# OpenMPPT2-DEBUG.net
KiCad netlist of a schematic drawn in Altium Designer
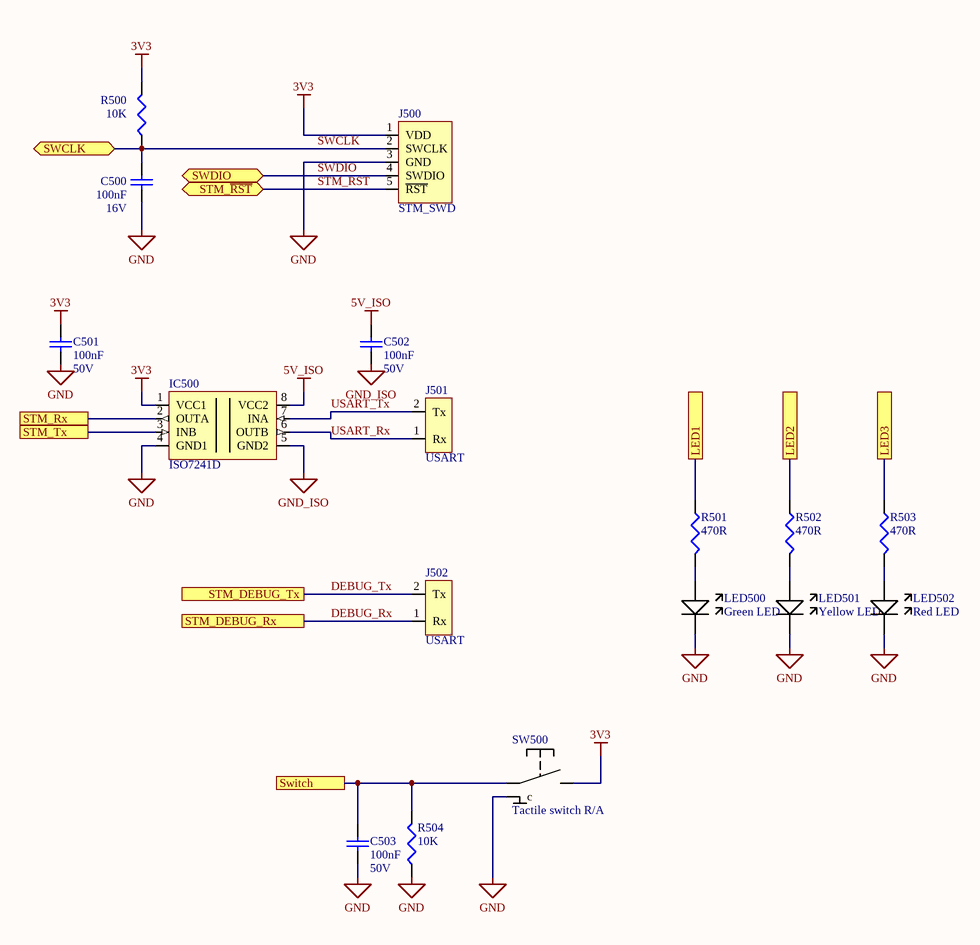
[diagram p0: OpenMPPT2-DEBUG.SchDoc]

(export (version "E")
  (design (tool "Eeschema 10.0.6"))
  (components
    (comp (ref "C500")
      (value "100nF")
      (footprint "C0603")
      (description "Capacitor, 100nF, 16V, X7R")
      (fields (field (name "VOLTAGE RATING") "16V"))
      (libsource (lib "SBT_Capacitors_Ceramic") (part "100nF/0603/CER/16V"))
    )
    (comp (ref "C501")
      (value "100nF")
      (footprint "C0603")
      (description "Capacitor, 100nF, 50V, X7R")
      (fields (field (name "VOLTAGE RATING") "50V"))
      (libsource (lib "SBT_Capacitors_Ceramic") (part "100nF/0603/CER/50V"))
    )
    (comp (ref "C502")
      (value "100nF")
      (footprint "C0603")
      (description "Capacitor, 100nF, 50V, X7R")
      (fields (field (name "VOLTAGE RATING") "50V"))
      (libsource (lib "SBT_Capacitors_Ceramic") (part "100nF/0603/CER/50V"))
    )
    (comp (ref "C503")
      (value "100nF")
      (footprint "C0603")
      (description "Capacitor, 100nF, 50V, X7R")
      (fields (field (name "VOLTAGE RATING") "50V"))
      (libsource (lib "SBT_Capacitors_Ceramic") (part "100nF/0603/CER/50V"))
    )
    (comp (ref "IC500")
      (value "ISO7241D")
      (footprint "SO-8")
      (description "1/1, 1Mbps Digital Isolator")
      (libsource (lib "SBT_ICs") (part "ISO7241D"))
    )
    (comp (ref "J500")
      (value "STM_SWD")
      (footprint "Header 2.54 5p")
      (description "SWD connector compliant with STM32 Nucleo boards")
      (libsource (lib "SBT_Connectors") (part "STM_SWD"))
    )
    (comp (ref "J501")
      (value "USART")
      (footprint "HEADER 2.54mm 2pin")
      (libsource (lib "SBT_Connectors") (part "USART"))
    )
    (comp (ref "J502")
      (value "USART")
      (footprint "HEADER 2.54mm 2pin")
      (libsource (lib "SBT_Connectors") (part "USART"))
    )
    (comp (ref "LED500")
      (value "Green LED")
      (footprint "0603")
      (description "LED, Green, 0603")
      (libsource (lib "SBT_LEDs") (part "KPT-1608SGC"))
    )
    (comp (ref "LED501")
      (value "Yellow LED")
      (footprint "0603")
      (description "LED, Yellow, 0603")
      (libsource (lib "SBT_LEDs") (part "KPT-2012YC"))
    )
    (comp (ref "LED502")
      (value "Red LED")
      (footprint "0603")
      (description "LED, Red, 0603")
      (libsource (lib "SBT_LEDs") (part "KPT-2012EC"))
    )
    (comp (ref "R500")
      (value "10K")
      (footprint "0603")
      (description "Resistor, 10K, 1%, 0.063W, 50V, 100PPM, 0603")
      (libsource (lib "SBT_Resistors_SMD") (part "10K/0603/0063W/50V"))
    )
    (comp (ref "R501")
      (value "470R")
      (footprint "0603")
      (description "Resistor, 470R, 1%, 0.125W, 50V, 100PPM, 0603")
      (libsource (lib "SBT_Resistors_SMD") (part "470/0603/0125W/50V"))
    )
    (comp (ref "R502")
      (value "470R")
      (footprint "0603")
      (description "Resistor, 470R, 1%, 0.125W, 50V, 100PPM, 0603")
      (libsource (lib "SBT_Resistors_SMD") (part "470/0603/0125W/50V"))
    )
    (comp (ref "R503")
      (value "470R")
      (footprint "0603")
      (description "Resistor, 470R, 1%, 0.125W, 50V, 100PPM, 0603")
      (libsource (lib "SBT_Resistors_SMD") (part "470/0603/0125W/50V"))
    )
    (comp (ref "R504")
      (value "10K")
      (footprint "0603")
      (description "Resistor, 10K, 1%, 0.063W, 50V, 100PPM, 0603")
      (libsource (lib "SBT_Resistors_SMD") (part "10K/0603/0063W/50V"))
    )
    (comp (ref "SW500")
      (value "Tactile switch R/A")
      (footprint "TactSW RA")
      (description "Tactile switch angled")
      (libsource (lib "SBT_DannyLib") (part "TactSwitch"))
    )
  )
  (nets
    (net (code "1") (name "/DEBUG_Rx") (class "Default")
      (node (ref "J502") (pin "1") (pinfunction "Rx_1") (pintype "passive"))
    )
    (net (code "2") (name "/DEBUG_Tx") (class "Default")
      (node (ref "J502") (pin "2") (pinfunction "Tx_2") (pintype "passive"))
    )
    (net (code "3") (name "/LED1") (class "Default")
      (node (ref "R501") (pin "1") (pinfunction "1_1") (pintype "passive"))
    )
    (net (code "4") (name "/LED2") (class "Default")
      (node (ref "R502") (pin "1") (pinfunction "1_1") (pintype "passive"))
    )
    (net (code "5") (name "/LED3") (class "Default")
      (node (ref "R503") (pin "1") (pinfunction "1_1") (pintype "passive"))
    )
    (net (code "6") (name "/STM_Rx") (class "Default")
      (node (ref "IC500") (pin "2") (pinfunction "OUTA_2") (pintype "output"))
    )
    (net (code "7") (name "/STM_Tx") (class "Default")
      (node (ref "IC500") (pin "3") (pinfunction "INB_3") (pintype "input"))
    )
    (net (code "8") (name "/STM_~{RST}") (class "Default")
      (node (ref "J500") (pin "5") (pinfunction "~{RST}_5") (pintype "passive"))
    )
    (net (code "9") (name "/SWCLK") (class "Default")
      (node (ref "C500") (pin "1") (pinfunction "1_1") (pintype "passive"))
      (node (ref "J500") (pin "2") (pinfunction "SWCLK_2") (pintype "passive"))
      (node (ref "R500") (pin "1") (pinfunction "1_1") (pintype "passive"))
    )
    (net (code "10") (name "/SWDIO") (class "Default")
      (node (ref "J500") (pin "4") (pinfunction "SWDIO_4") (pintype "passive"))
    )
    (net (code "11") (name "/Switch") (class "Default")
      (node (ref "C503") (pin "2") (pinfunction "2_2") (pintype "passive"))
      (node (ref "R504") (pin "2") (pinfunction "2_2") (pintype "passive"))
      (node (ref "SW500") (pin "1") (pinfunction "1_1") (pintype "passive"))
    )
    (net (code "12") (name "/USART_Rx") (class "Default")
      (node (ref "IC500") (pin "6") (pinfunction "OUTB_6") (pintype "output"))
      (node (ref "J501") (pin "1") (pinfunction "Rx_1") (pintype "passive"))
    )
    (net (code "13") (name "/USART_Tx") (class "Default")
      (node (ref "IC500") (pin "7") (pinfunction "INA_7") (pintype "input"))
      (node (ref "J501") (pin "2") (pinfunction "Tx_2") (pintype "passive"))
    )
    (net (code "14") (name "3V3") (class "Default")
      (node (ref "C501") (pin "2") (pinfunction "2_2") (pintype "passive"))
      (node (ref "IC500") (pin "1") (pinfunction "VCC1_1") (pintype "power_in"))
      (node (ref "J500") (pin "1") (pinfunction "VDD_1") (pintype "passive"))
      (node (ref "R500") (pin "2") (pinfunction "2_2") (pintype "passive"))
      (node (ref "SW500") (pin "2") (pinfunction "2_2") (pintype "passive"))
    )
    (net (code "15") (name "5V_ISO") (class "Default")
      (node (ref "C502") (pin "2") (pinfunction "2_2") (pintype "passive"))
      (node (ref "IC500") (pin "8") (pinfunction "VCC2_8") (pintype "power_in"))
    )
    (net (code "16") (name "GND") (class "Default")
      (node (ref "C500") (pin "2") (pinfunction "2_2") (pintype "passive"))
      (node (ref "C501") (pin "1") (pinfunction "1_1") (pintype "passive"))
      (node (ref "C503") (pin "1") (pinfunction "1_1") (pintype "passive"))
      (node (ref "IC500") (pin "4") (pinfunction "GND1_4") (pintype "power_in"))
      (node (ref "J500") (pin "3") (pinfunction "GND_3") (pintype "passive"))
      (node (ref "LED500") (pin "K") (pinfunction "K_K") (pintype "power_in"))
      (node (ref "LED501") (pin "K") (pinfunction "K_K") (pintype "power_in"))
      (node (ref "LED502") (pin "K") (pinfunction "K_K") (pintype "power_in"))
      (node (ref "R504") (pin "1") (pinfunction "1_1") (pintype "passive"))
      (node (ref "SW500") (pin "0") (pinfunction "c_0") (pintype "passive"))
    )
    (net (code "17") (name "GND_ISO") (class "Default")
      (node (ref "C502") (pin "1") (pinfunction "1_1") (pintype "passive"))
      (node (ref "IC500") (pin "5") (pinfunction "GND2_5") (pintype "power_in"))
    )
    (net (code "18") (name "Net-(LED500-PadA)") (class "Default")
      (node (ref "LED500") (pin "A") (pinfunction "A_A") (pintype "power_in"))
      (node (ref "R501") (pin "2") (pinfunction "2_2") (pintype "passive"))
    )
    (net (code "19") (name "Net-(LED501-PadA)") (class "Default")
      (node (ref "LED501") (pin "A") (pinfunction "A_A") (pintype "power_in"))
      (node (ref "R502") (pin "2") (pinfunction "2_2") (pintype "passive"))
    )
    (net (code "20") (name "Net-(LED502-PadA)") (class "Default")
      (node (ref "LED502") (pin "A") (pinfunction "A_A") (pintype "power_in"))
      (node (ref "R503") (pin "2") (pinfunction "2_2") (pintype "passive"))
    )
  )
)
